# eps_bb1.net
KiCad netlist of a schematic drawn in Altium Designer
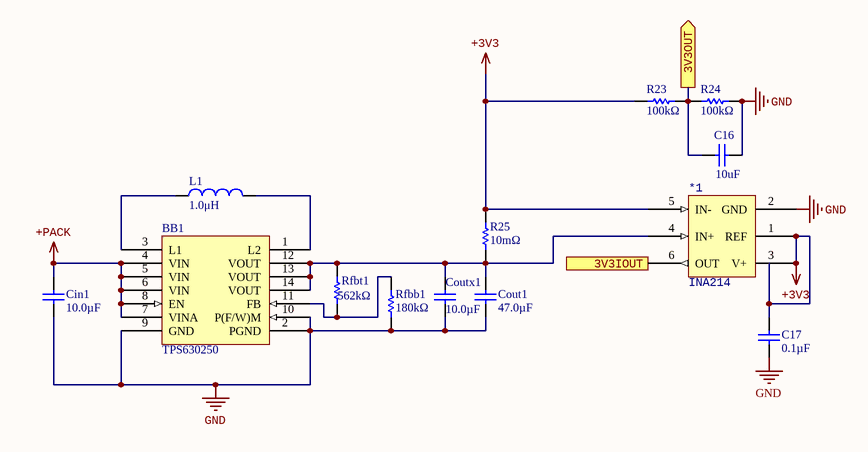
[diagram p0: eps_bb1.SchDoc]

(export (version "E")
  (design (tool "Eeschema 10.0.6"))
  (components
    (comp (ref "*1")
      (value "INA214")
      (footprint "SOT65P210X110-6N")
      (description "Current monitor")
      (libsource (lib "EPS") (part "INA214"))
    )
    (comp (ref "BB1")
      (value "TPS630250")
      (footprint "RNC0014A")
      (description "Buck-boost converter")
      (libsource (lib "heron-general") (part "TPS630250"))
    )
    (comp (ref "C16")
      (value "10uF")
      (footprint "1608[0603]")
      (description "Capacitor")
      (fields (field (name "PUBLISHER") "Altium Limited"))
      (libsource (lib "Miscellaneous Devices") (part "Cap"))
    )
    (comp (ref "C17")
      (value "0.1µF")
      (footprint "1608[0603]")
      (description "Capacitor (Semiconductor SIM Model)")
      (fields (field (name "PUBLISHER") "Altium Limited"))
      (libsource (lib "Miscellaneous Devices") (part "Cap Semi"))
    )
    (comp (ref "Cin1")
      (value "10.0µF")
      (footprint "1608[0603]")
      (description "Capacitor")
      (fields (field (name "PUBLISHER") "Altium Limited"))
      (libsource (lib "Miscellaneous Devices") (part "Cap"))
    )
    (comp (ref "Cout1")
      (value "47.0µF")
      (footprint "1608[0603]")
      (description "Capacitor")
      (fields (field (name "PUBLISHER") "Altium Limited"))
      (libsource (lib "Miscellaneous Devices") (part "Cap"))
    )
    (comp (ref "Coutx1")
      (value "10.0µF")
      (footprint "1608[0603]")
      (description "Capacitor")
      (fields (field (name "PUBLISHER") "Altium Limited"))
      (libsource (lib "Miscellaneous Devices") (part "Cap"))
    )
    (comp (ref "L1")
      (value "1.0μH")
      (footprint "1608[0603]")
      (description "Inductor")
      (fields (field (name "PUBLISHER") "Altium Limited"))
      (libsource (lib "Miscellaneous Devices") (part "Inductor"))
    )
    (comp (ref "R23")
      (value "100kΩ")
      (footprint "1608[0603]")
      (description "Resistor")
      (fields (field (name "PUBLISHER") "Altium Limited"))
      (libsource (lib "Miscellaneous Devices") (part "Res1"))
    )
    (comp (ref "R24")
      (value "100kΩ")
      (footprint "1608[0603]")
      (description "Resistor")
      (fields (field (name "PUBLISHER") "Altium Limited"))
      (libsource (lib "Miscellaneous Devices") (part "Res1"))
    )
    (comp (ref "R25")
      (value "10mΩ")
      (footprint "1608[0603]")
      (description "Resistor")
      (fields (field (name "PUBLISHER") "Altium Limited"))
      (libsource (lib "Miscellaneous Devices") (part "Res1"))
    )
    (comp (ref "Rfbb1")
      (value "180kΩ")
      (footprint "1608[0603]")
      (description "Resistor")
      (fields (field (name "PUBLISHER") "Altium Limited"))
      (libsource (lib "Miscellaneous Devices") (part "Res1"))
    )
    (comp (ref "Rfbt1")
      (value "562kΩ")
      (footprint "1608[0603]")
      (description "Resistor")
      (fields (field (name "PUBLISHER") "Altium Limited"))
      (libsource (lib "Miscellaneous Devices") (part "Res1"))
    )
  )
  (nets
    (net (code "1") (name "+3V3") (class "Default")
      (node (ref "*1") (pin "1") (pinfunction "REF_1") (pintype "passive"))
      (node (ref "*1") (pin "3") (pinfunction "V+_3") (pintype "power_in"))
      (node (ref "*1") (pin "5") (pinfunction "IN-_5") (pintype "input"))
      (node (ref "C17") (pin "2") (pinfunction "2_2") (pintype "passive"))
      (node (ref "R23") (pin "1") (pinfunction "1_1") (pintype "passive"))
      (node (ref "R25") (pin "2") (pinfunction "2_2") (pintype "passive"))
    )
    (net (code "2") (name "+PACK") (class "Default")
      (node (ref "BB1") (pin "4") (pinfunction "VIN_4") (pintype "power_in"))
      (node (ref "BB1") (pin "5") (pinfunction "VIN_5") (pintype "power_in"))
      (node (ref "BB1") (pin "6") (pinfunction "VIN_6") (pintype "power_in"))
      (node (ref "BB1") (pin "7") (pinfunction "VINA_7") (pintype "power_in"))
      (node (ref "BB1") (pin "8") (pinfunction "EN_8") (pintype "input"))
      (node (ref "Cin1") (pin "2") (pinfunction "2_2") (pintype "passive"))
    )
    (net (code "3") (name "/3V3IOUT") (class "Default")
      (node (ref "*1") (pin "6") (pinfunction "OUT_6") (pintype "output"))
    )
    (net (code "4") (name "/3V3OUT") (class "Default")
      (node (ref "C16") (pin "2") (pinfunction "2_2") (pintype "passive"))
      (node (ref "R23") (pin "2") (pinfunction "2_2") (pintype "passive"))
      (node (ref "R24") (pin "1") (pinfunction "1_1") (pintype "passive"))
    )
    (net (code "5") (name "GND") (class "Default")
      (node (ref "*1") (pin "2") (pinfunction "GND_2") (pintype "power_in"))
      (node (ref "BB1") (pin "10") (pinfunction "P(F/W)M_10") (pintype "input"))
      (node (ref "BB1") (pin "2") (pinfunction "PGND_2") (pintype "power_in"))
      (node (ref "BB1") (pin "9") (pinfunction "GND_9") (pintype "power_in"))
      (node (ref "C16") (pin "1") (pinfunction "1_1") (pintype "passive"))
      (node (ref "C17") (pin "1") (pinfunction "1_1") (pintype "passive"))
      (node (ref "Cin1") (pin "1") (pinfunction "1_1") (pintype "passive"))
      (node (ref "Cout1") (pin "1") (pinfunction "1_1") (pintype "passive"))
      (node (ref "Coutx1") (pin "1") (pinfunction "1_1") (pintype "passive"))
      (node (ref "R24") (pin "2") (pinfunction "2_2") (pintype "passive"))
      (node (ref "Rfbb1") (pin "1") (pinfunction "1_1") (pintype "passive"))
    )
    (net (code "6") (name "Net-(*1-IN+)") (class "Default")
      (node (ref "*1") (pin "4") (pinfunction "IN+_4") (pintype "input"))
      (node (ref "BB1") (pin "12") (pinfunction "VOUT_12") (pintype "passive"))
      (node (ref "BB1") (pin "13") (pinfunction "VOUT_13") (pintype "passive"))
      (node (ref "BB1") (pin "14") (pinfunction "VOUT_14") (pintype "passive"))
      (node (ref "Cout1") (pin "2") (pinfunction "2_2") (pintype "passive"))
      (node (ref "Coutx1") (pin "2") (pinfunction "2_2") (pintype "passive"))
      (node (ref "R25") (pin "1") (pinfunction "1_1") (pintype "passive"))
      (node (ref "Rfbt1") (pin "1") (pinfunction "1_1") (pintype "passive"))
    )
    (net (code "7") (name "Net-(BB1-FB)") (class "Default")
      (node (ref "BB1") (pin "11") (pinfunction "FB_11") (pintype "input"))
      (node (ref "Rfbb1") (pin "2") (pinfunction "2_2") (pintype "passive"))
      (node (ref "Rfbt1") (pin "2") (pinfunction "2_2") (pintype "passive"))
    )
    (net (code "8") (name "Net-(BB1-L1)") (class "Default")
      (node (ref "BB1") (pin "3") (pinfunction "L1_3") (pintype "power_in"))
      (node (ref "L1") (pin "1") (pinfunction "1_1") (pintype "passive"))
    )
    (net (code "9") (name "Net-(BB1-L2)") (class "Default")
      (node (ref "BB1") (pin "1") (pinfunction "L2_1") (pintype "power_in"))
      (node (ref "L1") (pin "2") (pinfunction "2_2") (pintype "passive"))
    )
  )
)
